# ip_phone_c_codec.net
KiCad netlist of a schematic drawn in Altium Designer
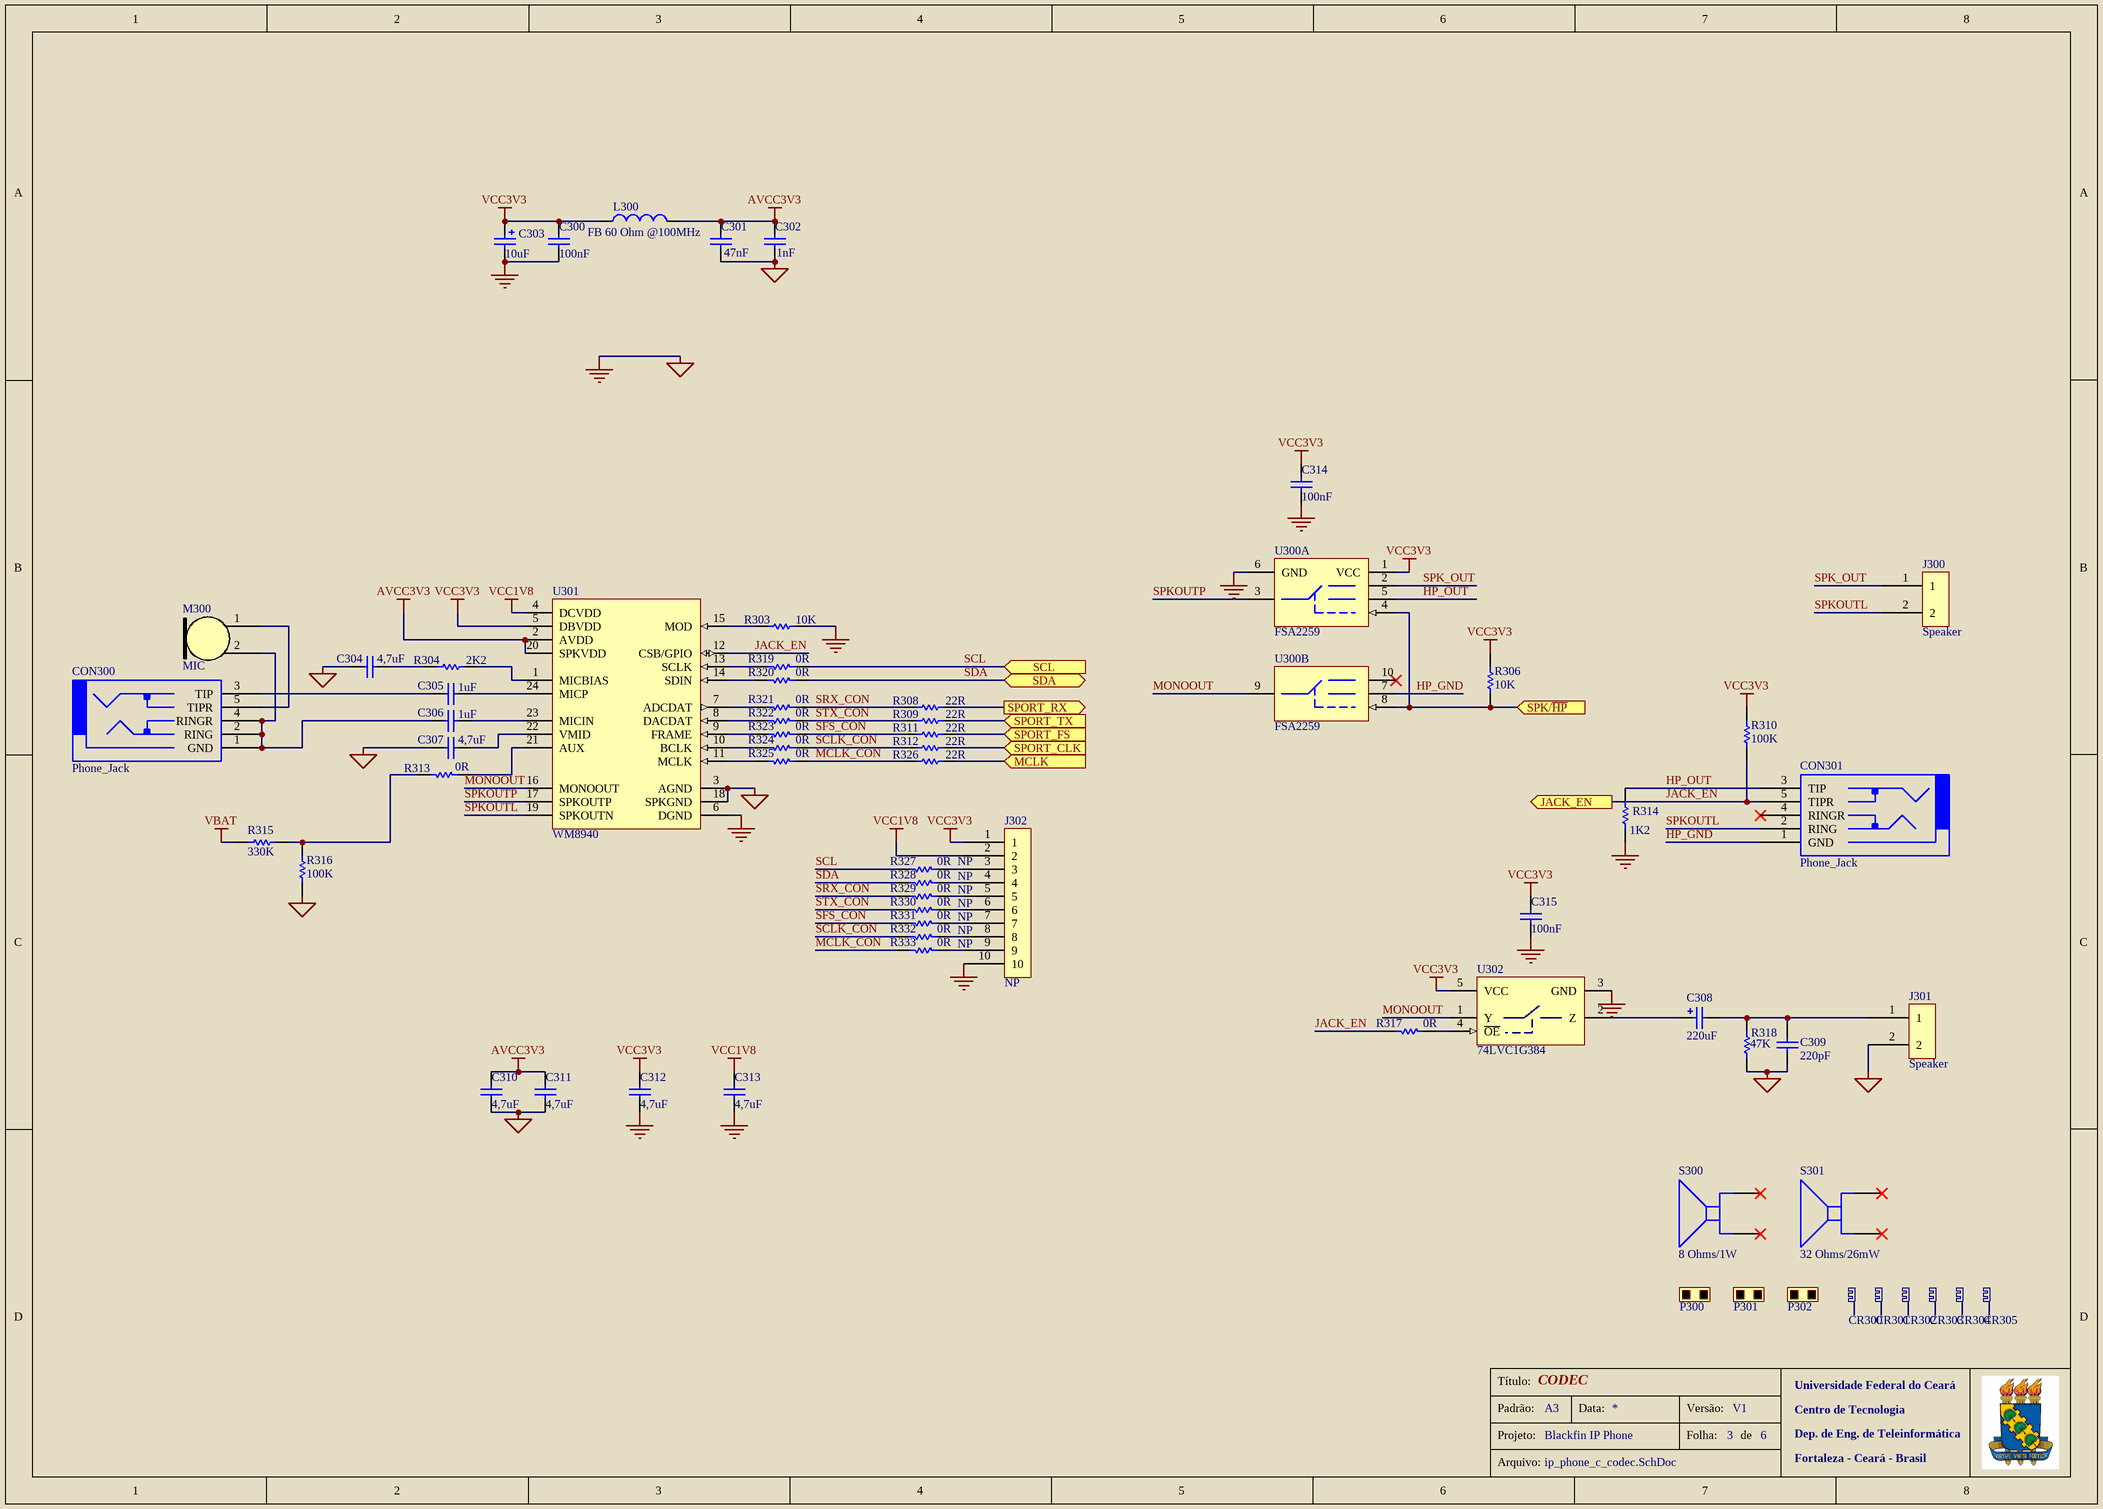
[diagram p0: ip_phone_c_codec.SchDoc]

(export (version "E")
  (design (tool "Eeschema 10.0.6"))
  (components
    (comp (ref "C300")
      (value "100nF")
      (footprint "ip_phone:CC1005-0402")
      (description "MLCC - SMD/SMT 100nF 16V 10% 0402")
      (fields (field (name "EVENDORPART#") "810-C1005X7R1C104K") (field (name "MANUFACTURER") "TDK"))
      (libsource (lib "ip_phone") (part "Capacitor"))
    )
    (comp (ref "C301")
      (value "47nF")
      (footprint "ip_phone:CC1005-0402")
      (description "MLCC - SMD/SMT 47nF 16V 10% 0402")
      (fields (field (name "EVENDORPART#") "311-1334-1-ND") (field (name "MANUFACTURER") "Yageo"))
      (libsource (lib "ip_phone") (part "Capacitor"))
    )
    (comp (ref "C302")
      (value "1nF")
      (footprint "ip_phone:CC1005-0402")
      (description "MLCC - SMD/SMT 1nF 16V 10% 0402")
      (fields (field (name "EVENDORPART#") "311-1352-1-ND") (field (name "MANUFACTURER") "Yageo"))
      (libsource (lib "ip_phone") (part "Capacitor"))
    )
    (comp (ref "C303")
      (value "10uF")
      (footprint "ip_phone:VE-100M0JTR-0305")
      (description "Aluminum Electrolytic Capacitors - SMD 6.3 Volts 10uF 20%")
      (fields (field (name "EVENDORPART#") "140-VE100M0JTR0305") (field (name "PART#") "VE-100M0JTR-0305"))
      (libsource (lib "ip_phone") (part "Capacitor_Electrolytic"))
    )
    (comp (ref "C304")
      (value "4,7uF")
      (footprint "ip_phone:CC1005-0402")
      (description "MLCC - SMD/SMT 4.7uF 20% 6.3Volts 0402")
      (fields (field (name "EVENDORPART#") "810-C1005X5R0J475M") (field (name "MANUFACTURER") "TDK"))
      (libsource (lib "ip_phone") (part "Capacitor"))
    )
    (comp (ref "C305")
      (value "1uF")
      (footprint "ip_phone:CC1005-0402")
      (description "CAP CER 1.0UF 6.3V 20% X5R 0402")
      (fields
        (field (name "EVENDORPART#") "490-1319-1-ND")
        (field (name "MANUFACTURER") "Murata Electronics North America")
      )
      (libsource (lib "ip_phone") (part "Capacitor"))
    )
    (comp (ref "C306")
      (value "1uF")
      (footprint "ip_phone:CC1005-0402")
      (description "CAP CER 1.0UF 6.3V 20% X5R 0402")
      (fields
        (field (name "EVENDORPART#") "490-1319-1-ND")
        (field (name "MANUFACTURER") "Murata Electronics North America")
      )
      (libsource (lib "ip_phone") (part "Capacitor"))
    )
    (comp (ref "C307")
      (value "4,7uF")
      (footprint "ip_phone:CC1005-0402")
      (description "MLCC - SMD/SMT 4.7uF 20% 6.3Volts 0402")
      (fields (field (name "EVENDORPART#") "810-C1005X5R0J475M") (field (name "MANUFACTURER") "TDK"))
      (libsource (lib "ip_phone") (part "Capacitor"))
    )
    (comp (ref "C308")
      (value "220uF")
      (description "Tantalum Capacitor - SMD 6.3 Volts 220uF 10%")
      (fields (field (name "EVENDORPART#") "80-T491D227K006") (field (name "PART#") "T491D227K006AT"))
      (libsource (lib "ip_phone") (part "Capacitor_Electrolytic"))
    )
    (comp (ref "C309")
      (value "220pF")
      (footprint "ip_phone:CC1005-0402")
      (description "Capacitor 220pF 0402")
      (fields (field (name "EVENDORPART#") "311-1035-1-ND") (field (name "MANUFACTURER") "Yageo"))
      (libsource (lib "ip_phone") (part "Capacitor"))
    )
    (comp (ref "C310")
      (value "4,7uF")
      (footprint "ip_phone:CC1005-0402")
      (description "MLCC - SMD/SMT 4.7uF 20% 6.3Volts 0402")
      (fields (field (name "EVENDORPART#") "810-C1005X5R0J475M") (field (name "MANUFACTURER") "TDK"))
      (libsource (lib "ip_phone") (part "Capacitor"))
    )
    (comp (ref "C311")
      (value "4,7uF")
      (footprint "ip_phone:CC1005-0402")
      (description "MLCC - SMD/SMT 4.7uF 20% 6.3Volts 0402")
      (fields (field (name "EVENDORPART#") "810-C1005X5R0J475M") (field (name "MANUFACTURER") "TDK"))
      (libsource (lib "ip_phone") (part "Capacitor"))
    )
    (comp (ref "C312")
      (value "4,7uF")
      (footprint "ip_phone:CC1005-0402")
      (description "MLCC - SMD/SMT 4.7uF 20% 6.3Volts 0402")
      (fields (field (name "EVENDORPART#") "810-C1005X5R0J475M") (field (name "MANUFACTURER") "TDK"))
      (libsource (lib "ip_phone") (part "Capacitor"))
    )
    (comp (ref "C313")
      (value "4,7uF")
      (footprint "ip_phone:CC1005-0402")
      (description "MLCC - SMD/SMT 4.7uF 20% 6.3Volts 0402")
      (fields (field (name "EVENDORPART#") "810-C1005X5R0J475M") (field (name "MANUFACTURER") "TDK"))
      (libsource (lib "ip_phone") (part "Capacitor"))
    )
    (comp (ref "C314")
      (value "100nF")
      (footprint "ip_phone:CC1005-0402")
      (description "MLCC - SMD/SMT 0.1UF 16V 10% 0402")
      (fields (field (name "EVENDORPART#") "810-C1005X7R1C104K") (field (name "MANUFACTURER") "TDK"))
      (libsource (lib "ip_phone") (part "Capacitor"))
    )
    (comp (ref "C315")
      (value "100nF")
      (footprint "ip_phone:CC1005-0402")
      (description "MLCC - SMD/SMT 0.1UF 16V 10% 0402")
      (fields (field (name "EVENDORPART#") "810-C1005X7R1C104K") (field (name "MANUFACTURER") "TDK"))
      (libsource (lib "ip_phone") (part "Capacitor"))
    )
    (comp (ref "CON300")
      (value "Phone_Jack")
      (footprint "ip_phone:Phone_Jack")
      (fields
        (field (name "EVENDORPART#") "CP1-2535SJCT-ND")
        (field (name "MANUFACTURER") "CUI Inc")
        (field (name "PART#") "SJ1-2535-SMT")
      )
      (libsource (lib "ip_phone") (part "Phone_Jack_1"))
    )
    (comp (ref "CON301")
      (value "Phone_Jack")
      (footprint "ip_phone:Phone_Jack")
      (fields
        (field (name "EVENDORPART#") "CP1-2535SJCT-ND")
        (field (name "MANUFACTURER") "CUI Inc")
        (field (name "PART#") "SJ1-2535-SMT")
      )
      (libsource (lib "") (part "Phone_Jack_1_1"))
    )
    (comp (ref "CR300")
      (value "Crimp")
      (description "Socket Crimp")
      (fields (field (name "EVENDORPART#") "656-ILZC3A115000") (field (name "PART#") "IL-Z-C3-A-1-15000"))
      (libsource (lib "ip_phone") (part "Crimp"))
    )
    (comp (ref "CR301")
      (value "Crimp")
      (description "Socket Crimp")
      (fields (field (name "EVENDORPART#") "656-ILZC3A115000") (field (name "PART#") "IL-Z-C3-A-1-15000"))
      (libsource (lib "ip_phone") (part "Crimp"))
    )
    (comp (ref "CR302")
      (value "Crimp")
      (description "Socket Crimp")
      (fields (field (name "EVENDORPART#") "656-ILZC3A115000") (field (name "PART#") "IL-Z-C3-A-1-15000"))
      (libsource (lib "ip_phone") (part "Crimp"))
    )
    (comp (ref "CR303")
      (value "Crimp")
      (description "Socket Crimp")
      (fields (field (name "EVENDORPART#") "656-ILZC3A115000") (field (name "PART#") "IL-Z-C3-A-1-15000"))
      (libsource (lib "ip_phone") (part "Crimp"))
    )
    (comp (ref "CR304")
      (value "Crimp")
      (description "Socket Crimp")
      (fields (field (name "EVENDORPART#") "656-ILZC3A115000") (field (name "PART#") "IL-Z-C3-A-1-15000"))
      (libsource (lib "ip_phone") (part "Crimp"))
    )
    (comp (ref "CR305")
      (value "Crimp")
      (description "Socket Crimp")
      (fields (field (name "EVENDORPART#") "656-ILZC3A115000") (field (name "PART#") "IL-Z-C3-A-1-15000"))
      (libsource (lib "ip_phone") (part "Crimp"))
    )
    (comp (ref "J300")
      (value "Speaker")
      (footprint "ip_phone:CON_IL-Z-2PL")
      (description "Connector 2 Pin 1.25mm Male")
      (fields
        (field (name "EVENDORPART#") "656-IL-Z-2PL-SMTYE")
        (field (name "MANUFACTURER") "JAE Electronics")
      )
      (libsource (lib "ip_phone") (part "Speaker_con"))
    )
    (comp (ref "J301")
      (value "Speaker")
      (footprint "ip_phone:CON_IL-Z-2PL")
      (description "Connector 2 Pin 1.25mm Male")
      (fields
        (field (name "EVENDORPART#") "656-IL-Z-2PL-SMTYE")
        (field (name "MANUFACTURER") "JAE Electronics")
      )
      (libsource (lib "ip_phone") (part "Speaker_con"))
    )
    (comp (ref "J302")
      (value "CONN HEADER")
      (footprint "ip_phone:CONECTOR_10_PIN")
      (description "CONN HEADER .050\" 10POS PCB GOLD")
      (fields
        (field (name "EVENDORPART#") "S9014E-10-ND")
        (field (name "MANUFACTURER") "Sullins Connector Solutions")
        (field (name "NP") "NP")
      )
      (libsource (lib "ip_phone") (part "Conector 10pin"))
    )
    (comp (ref "L300")
      (value "FB 60 Ohm @100MHz")
      (footprint "ip_phone:INDUTOR_0603")
      (description "Ferrite Bead 60 Ohm @100MHz")
      (fields
        (field (name "EVENDORPART#") "667-EXC-3BP600H")
        (field (name "MANUFACTURER") "Panasonic Electronic Components")
      )
      (libsource (lib "ip_phone") (part "Inductor"))
    )
    (comp (ref "M300")
      (value "MIC")
      (footprint "ip_phone:CON_IL-Z-2PL")
      (description "Microphones -38DB 2VDC .5MA 2.2KOHM")
      (fields (field (name "PART#") "POM-2738P-C33-R") (field (name "MANUFACTURER") "PUI Audio"))
      (libsource (lib "ip_phone") (part "MIC"))
    )
    (comp (ref "P300")
      (value "Socket Housing")
      (description "Socket Housing 1.25mm 2 Pins")
      (fields (field (name "EVENDORPART#") "656-IL-Z-2S-S125C3") (field (name "PART#") "IL-Z-2S-S125C3"))
      (libsource (lib "ip_phone") (part "Socket Housing"))
    )
    (comp (ref "P301")
      (value "Socket Housing")
      (description "Socket Housing 1.25mm 2 Pins")
      (fields (field (name "EVENDORPART#") "656-IL-Z-2S-S125C3") (field (name "PART#") "IL-Z-2S-S125C3"))
      (libsource (lib "ip_phone") (part "Socket Housing"))
    )
    (comp (ref "P302")
      (value "Socket Housing")
      (description "Socket Housing 1.25mm 2 Pins")
      (fields (field (name "EVENDORPART#") "656-IL-Z-2S-S125C3") (field (name "PART#") "IL-Z-2S-S125C3"))
      (libsource (lib "ip_phone") (part "Socket Housing"))
    )
    (comp (ref "R303")
      (value "10K")
      (footprint "ip_phone:CR1005-0402")
      (description "Thick Film Resistors SMD 0402 10K 5%  1/16 W")
      (fields (field (name "EVENDORPART#") "311-10KJRCT-ND") (field (name "MANUFACTURER") "Yageo"))
      (libsource (lib "ip_phone") (part "Resistor"))
    )
    (comp (ref "R304")
      (value "2K2")
      (footprint "ip_phone:CR1005-0402")
      (description "Thick Film Resistors SMD 0402 2K2 5%  1/16 W")
      (fields (field (name "EVENDORPART#") "311-2.2KJRCT-ND") (field (name "MANUFACTURER") "Yageo"))
      (libsource (lib "ip_phone") (part "Resistor"))
    )
    (comp (ref "R306")
      (value "10K")
      (footprint "ip_phone:CR1005-0402")
      (description "Thick Film Resistors SMD 0402 10K 5%  1/16 W")
      (fields (field (name "EVENDORPART#") "311-10KJRCT-ND") (field (name "MANUFACTURER") "Yageo"))
      (libsource (lib "ip_phone") (part "Resistor"))
    )
    (comp (ref "R308")
      (value "22R")
      (footprint "ip_phone:CR1005-0402")
      (description "Thick Film Resistors SMD 0402 22R 5%  1/16 W")
      (fields (field (name "EVENDORPART#") "71-CRCW0402J-22-E3") (field (name "MANUFACTURER") "Vishay/Dale"))
      (libsource (lib "ip_phone") (part "Resistor"))
    )
    (comp (ref "R309")
      (value "22R")
      (footprint "ip_phone:CR1005-0402")
      (description "Thick Film Resistors SMD 0402 22R 5%  1/16 W")
      (fields (field (name "EVENDORPART#") "71-CRCW0402J-22-E3") (field (name "MANUFACTURER") "Vishay/Dale"))
      (libsource (lib "ip_phone") (part "Resistor"))
    )
    (comp (ref "R310")
      (value "100K")
      (footprint "ip_phone:CR1005-0402")
      (description "Thick Film Resistors SMD 0402 100K 5%  1/16 W")
      (fields (field (name "EVENDORPART#") "311-100KJRCT-ND") (field (name "MANUFACTURER") "Yageo"))
      (libsource (lib "ip_phone") (part "Resistor"))
    )
    (comp (ref "R311")
      (value "22R")
      (footprint "ip_phone:CR1005-0402")
      (description "Thick Film Resistors SMD 0402 22R 5%  1/16 W")
      (fields (field (name "EVENDORPART#") "71-CRCW0402J-22-E3") (field (name "MANUFACTURER") "Vishay/Dale"))
      (libsource (lib "ip_phone") (part "Resistor"))
    )
    (comp (ref "R312")
      (value "22R")
      (footprint "ip_phone:CR1005-0402")
      (description "Thick Film Resistors SMD 0402 22R 5%  1/16 W")
      (fields (field (name "EVENDORPART#") "71-CRCW0402J-22-E3") (field (name "MANUFACTURER") "Vishay/Dale"))
      (libsource (lib "ip_phone") (part "Resistor"))
    )
    (comp (ref "R313")
      (value "0R")
      (footprint "ip_phone:CR1005-0402")
      (description "Thick Film Resistors 0402 1/16W Jumper")
      (fields
        (field (name "EVENDORPART#") "667-ERJ-2GE0R00X")
        (field (name "MANUFACTURER") "Panasonic Electronic Components")
      )
      (libsource (lib "ip_phone") (part "Resistor"))
    )
    (comp (ref "R314")
      (value "1K2")
      (footprint "ip_phone:CR1005-0402")
      (description "Thick Film Resistors SMD 0402 1K2 5%  1/16 W")
      (fields (field (name "EVENDORPART#") "311-1.2KJRCT-ND") (field (name "MANUFACTURER") "Yageo"))
      (libsource (lib "ip_phone") (part "Resistor"))
    )
    (comp (ref "R315")
      (value "330K")
      (footprint "ip_phone:CR1005-0402")
      (description "Thick Film Resistor 330K 1% 1/16W")
      (fields
        (field (name "EVENDORPART#") "RMCF0402FT330KCT-ND")
        (field (name "MANUFACTURER") "Stackpole Electronics Inc")
      )
      (libsource (lib "ip_phone") (part "Resistor"))
    )
    (comp (ref "R316")
      (value "100K")
      (footprint "ip_phone:CR1005-0402")
      (description "Thick Film Resistors SMD 0402 100K 5%  1/16 W")
      (fields (field (name "EVENDORPART#") "311-100KJRCT-ND") (field (name "MANUFACTURER") "Yageo"))
      (libsource (lib "ip_phone") (part "Resistor"))
    )
    (comp (ref "R317")
      (value "0R")
      (footprint "ip_phone:CR1005-0402")
      (description "Thick Film Resistors 0402 1/16W Jumper")
      (fields
        (field (name "EVENDORPART#") "667-ERJ-2GE0R00X")
        (field (name "MANUFACTURER") "Panasonic Electronic Components")
      )
      (libsource (lib "ip_phone") (part "Resistor"))
    )
    (comp (ref "R318")
      (value "47K")
      (footprint "ip_phone:CR1005-0402")
      (description "Thick Film Resistors SMD 0402 47K 5%  1/16 W")
      (fields (field (name "EVENDORPART#") "311-47KJRCT-ND") (field (name "MANUFACTURER") "Yageo"))
      (libsource (lib "ip_phone") (part "Resistor"))
    )
    (comp (ref "R319")
      (value "0R")
      (footprint "ip_phone:CR1005-0402")
      (description "Thick Film Resistors 0402 1/16W Jumper")
      (fields
        (field (name "EVENDORPART#") "667-ERJ-2GE0R00X")
        (field (name "MANUFACTURER") "Panasonic Electronic Components")
      )
      (libsource (lib "ip_phone") (part "Resistor"))
    )
    (comp (ref "R320")
      (value "0R")
      (footprint "ip_phone:CR1005-0402")
      (description "Thick Film Resistors 0402 1/16W Jumper")
      (fields
        (field (name "EVENDORPART#") "667-ERJ-2GE0R00X")
        (field (name "MANUFACTURER") "Panasonic Electronic Components")
      )
      (libsource (lib "ip_phone") (part "Resistor"))
    )
    (comp (ref "R321")
      (value "0R")
      (footprint "ip_phone:CR1005-0402")
      (description "Thick Film Resistors 0402 1/16W Jumper")
      (fields
        (field (name "EVENDORPART#") "667-ERJ-2GE0R00X")
        (field (name "MANUFACTURER") "Panasonic Electronic Components")
      )
      (libsource (lib "ip_phone") (part "Resistor"))
    )
    (comp (ref "R322")
      (value "0R")
      (footprint "ip_phone:CR1005-0402")
      (description "Thick Film Resistors 0402 1/16W Jumper")
      (fields
        (field (name "EVENDORPART#") "667-ERJ-2GE0R00X")
        (field (name "MANUFACTURER") "Panasonic Electronic Components")
      )
      (libsource (lib "ip_phone") (part "Resistor"))
    )
    (comp (ref "R323")
      (value "0R")
      (footprint "ip_phone:CR1005-0402")
      (description "Thick Film Resistors 0402 1/16W Jumper")
      (fields
        (field (name "EVENDORPART#") "667-ERJ-2GE0R00X")
        (field (name "MANUFACTURER") "Panasonic Electronic Components")
      )
      (libsource (lib "ip_phone") (part "Resistor"))
    )
    (comp (ref "R324")
      (value "0R")
      (footprint "ip_phone:CR1005-0402")
      (description "Thick Film Resistors 0402 1/16W Jumper")
      (fields
        (field (name "EVENDORPART#") "667-ERJ-2GE0R00X")
        (field (name "MANUFACTURER") "Panasonic Electronic Components")
      )
      (libsource (lib "ip_phone") (part "Resistor"))
    )
    (comp (ref "R325")
      (value "0R")
      (footprint "ip_phone:CR1005-0402")
      (description "Thick Film Resistors 0402 1/16W Jumper")
      (fields
        (field (name "EVENDORPART#") "667-ERJ-2GE0R00X")
        (field (name "MANUFACTURER") "Panasonic Electronic Components")
      )
      (libsource (lib "ip_phone") (part "Resistor"))
    )
    (comp (ref "R326")
      (value "22R")
      (footprint "ip_phone:CR1005-0402")
      (description "Thick Film Resistors SMD 0402 22R 5%  1/16 W")
      (fields (field (name "EVENDORPART#") "71-CRCW0402J-22-E3") (field (name "MANUFACTURER") "Vishay/Dale"))
      (libsource (lib "ip_phone") (part "Resistor"))
    )
    (comp (ref "R327")
      (value "0R")
      (footprint "ip_phone:CR1005-0402")
      (description "Thick Film Resistors 0402 1/16W Jumper")
      (fields
        (field (name "EVENDORPART#") "667-ERJ-2GE0R00X")
        (field (name "MANUFACTURER") "Panasonic Electronic Components")
        (field (name "NP") "NP")
      )
      (libsource (lib "ip_phone") (part "Resistor"))
    )
    (comp (ref "R328")
      (value "0R")
      (footprint "ip_phone:CR1005-0402")
      (description "Thick Film Resistors 0402 1/16W Jumper")
      (fields
        (field (name "EVENDORPART#") "667-ERJ-2GE0R00X")
        (field (name "MANUFACTURER") "Panasonic Electronic Components")
        (field (name "NP") "NP")
      )
      (libsource (lib "ip_phone") (part "Resistor"))
    )
    (comp (ref "R329")
      (value "0R")
      (footprint "ip_phone:CR1005-0402")
      (description "Thick Film Resistors 0402 1/16W Jumper")
      (fields
        (field (name "EVENDORPART#") "667-ERJ-2GE0R00X")
        (field (name "MANUFACTURER") "Panasonic Electronic Components")
        (field (name "NP") "NP")
      )
      (libsource (lib "ip_phone") (part "Resistor"))
    )
    (comp (ref "R330")
      (value "0R")
      (footprint "ip_phone:CR1005-0402")
      (description "Thick Film Resistors 0402 1/16W Jumper")
      (fields
        (field (name "EVENDORPART#") "667-ERJ-2GE0R00X")
        (field (name "MANUFACTURER") "Panasonic Electronic Components")
        (field (name "NP") "NP")
      )
      (libsource (lib "ip_phone") (part "Resistor"))
    )
    (comp (ref "R331")
      (value "0R")
      (footprint "ip_phone:CR1005-0402")
      (description "Thick Film Resistors 0402 1/16W Jumper")
      (fields
        (field (name "EVENDORPART#") "667-ERJ-2GE0R00X")
        (field (name "MANUFACTURER") "Panasonic Electronic Components")
        (field (name "NP") "NP")
      )
      (libsource (lib "ip_phone") (part "Resistor"))
    )
    (comp (ref "R332")
      (value "0R")
      (footprint "ip_phone:CR1005-0402")
      (description "Thick Film Resistors 0402 1/16W Jumper")
      (fields
        (field (name "EVENDORPART#") "667-ERJ-2GE0R00X")
        (field (name "MANUFACTURER") "Panasonic Electronic Components")
        (field (name "NP") "NP")
      )
      (libsource (lib "ip_phone") (part "Resistor"))
    )
    (comp (ref "R333")
      (value "0R")
      (footprint "ip_phone:CR1005-0402")
      (description "Thick Film Resistors 0402 1/16W Jumper")
      (fields
        (field (name "EVENDORPART#") "667-ERJ-2GE0R00X")
        (field (name "MANUFACTURER") "Panasonic Electronic Components")
        (field (name "NP") "NP")
      )
      (libsource (lib "ip_phone") (part "Resistor"))
    )
    (comp (ref "S300")
      (value "8 Ohms/1W")
      (description "Speaker 8 Ohms 1W")
      (fields (field (name "EVENDORPART#") "254-DS238-RO") (field (name "MANUFACTURER") "Kobitone"))
      (libsource (lib "ip_phone") (part "Speaker"))
    )
    (comp (ref "S301")
      (value "32 Ohms/26mW")
      (description "Dynamic Receiver 32Ohms 26mW 115dB 13mm D")
      (fields (field (name "EVENDORPART#") "254-DR132-RO") (field (name "MANUFACTURER") "Kobitone"))
      (libsource (lib "ip_phone") (part "Receiver"))
    )
    (comp (ref "U300")
      (value "FSA2259")
      (footprint "ip_phone:QFN-10FSA")
      (description "Analog Switch, Dual SPDT")
      (fields
        (field (name "EVENDORPART#") "512-FSA2259UMX")
        (field (name "MANUFACTURER") "Fairchild Semiconductor")
      )
      (libsource (lib "ip_phone") (part "FSA2259"))
    )
    (comp (ref "U301")
      (value "WM8940")
      (footprint "ip_phone:QFN24")
      (description "Mono Audio CODEC")
      (fields (field (name "EVENDORPART#") "238-WM8940GEFL/V") (field (name "PART#") "WM8940GEFL/V"))
      (libsource (lib "ip_phone") (part "WM8940"))
    )
    (comp (ref "U302")
      (value "74LVC1G384")
      (footprint "ip_phone:SOT753")
      (description "Low Voltage SPST Analog Switch")
      (fields (field (name "EVENDORPART#") "771-LVC1G384GV125") (field (name "PART#") "74LVC1G384GV,125"))
      (libsource (lib "ip_phone") (part "74LVC1G384"))
    )
  )
  (nets
    (net (code "1") (name "/HP_GND") (class "Default")
      (node (ref "CON301") (pin "1") (pinfunction "GND_1") (pintype "passive"))
      (node (ref "U300") (pin "7") (pinfunction "2B0_7") (pintype "passive"))
    )
    (net (code "2") (name "/HP_OUT") (class "Default")
      (node (ref "CON301") (pin "3") (pinfunction "TIP_3") (pintype "passive"))
      (node (ref "R314") (pin "1") (pinfunction "1_1") (pintype "passive"))
      (node (ref "U300") (pin "5") (pinfunction "1B0_5") (pintype "passive"))
    )
    (net (code "3") (name "/JACK_EN") (class "Default")
      (node (ref "CON301") (pin "5") (pinfunction "TIPR_5") (pintype "passive"))
      (node (ref "R310") (pin "1") (pinfunction "1_1") (pintype "passive"))
      (node (ref "R317") (pin "2") (pinfunction "2_2") (pintype "passive"))
      (node (ref "U301") (pin "12") (pinfunction "CSB/GPIO_12") (pintype "bidirectional"))
    )
    (net (code "4") (name "/MCLK") (class "Default")
      (node (ref "R326") (pin "2") (pinfunction "2_2") (pintype "passive"))
    )
    (net (code "5") (name "/MCLK_CON") (class "Default")
      (node (ref "R325") (pin "1") (pinfunction "1_1") (pintype "passive"))
      (node (ref "R326") (pin "1") (pinfunction "1_1") (pintype "passive"))
      (node (ref "R333") (pin "2") (pinfunction "2_2") (pintype "passive"))
    )
    (net (code "6") (name "/MONOOUT") (class "Default")
      (node (ref "U300") (pin "9") (pinfunction "2A_9") (pintype "passive"))
      (node (ref "U301") (pin "16") (pinfunction "MONOOUT_16") (pintype "passive"))
      (node (ref "U302") (pin "1") (pinfunction "Y_1") (pintype "passive"))
    )
    (net (code "7") (name "/SCL") (class "Default")
      (node (ref "R319") (pin "1") (pinfunction "1_1") (pintype "passive"))
      (node (ref "R327") (pin "2") (pinfunction "2_2") (pintype "passive"))
    )
    (net (code "8") (name "/SCLK_CON") (class "Default")
      (node (ref "R312") (pin "1") (pinfunction "1_1") (pintype "passive"))
      (node (ref "R324") (pin "1") (pinfunction "1_1") (pintype "passive"))
      (node (ref "R332") (pin "2") (pinfunction "2_2") (pintype "passive"))
    )
    (net (code "9") (name "/SDA") (class "Default")
      (node (ref "R320") (pin "1") (pinfunction "1_1") (pintype "passive"))
      (node (ref "R328") (pin "2") (pinfunction "2_2") (pintype "passive"))
    )
    (net (code "10") (name "/SFS_CON") (class "Default")
      (node (ref "R311") (pin "1") (pinfunction "1_1") (pintype "passive"))
      (node (ref "R323") (pin "1") (pinfunction "1_1") (pintype "passive"))
      (node (ref "R331") (pin "2") (pinfunction "2_2") (pintype "passive"))
    )
    (net (code "11") (name "/SPKOUTL") (class "Default")
      (node (ref "CON301") (pin "2") (pinfunction "RING_2") (pintype "passive"))
      (node (ref "J300") (pin "2") (pinfunction "2_2") (pintype "passive"))
      (node (ref "U301") (pin "19") (pinfunction "SPKOUTN_19") (pintype "passive"))
    )
    (net (code "12") (name "/SPKOUTP") (class "Default")
      (node (ref "U300") (pin "3") (pinfunction "1A_3") (pintype "passive"))
      (node (ref "U301") (pin "17") (pinfunction "SPKOUTP_17") (pintype "passive"))
    )
    (net (code "13") (name "/SPK_OUT") (class "Default")
      (node (ref "J300") (pin "1") (pinfunction "1_1") (pintype "passive"))
      (node (ref "U300") (pin "2") (pinfunction "1B1_2") (pintype "passive"))
    )
    (net (code "14") (name "/SPK{slash}~{HP}") (class "Default")
      (node (ref "R306") (pin "1") (pinfunction "1_1") (pintype "passive"))
      (node (ref "U300") (pin "4") (pinfunction "S1_4") (pintype "input"))
      (node (ref "U300") (pin "8") (pinfunction "S2_8") (pintype "input"))
    )
    (net (code "15") (name "/SPORT_CLK") (class "Default")
      (node (ref "R312") (pin "2") (pinfunction "2_2") (pintype "passive"))
    )
    (net (code "16") (name "/SPORT_FS") (class "Default")
      (node (ref "R311") (pin "2") (pinfunction "2_2") (pintype "passive"))
    )
    (net (code "17") (name "/SPORT_RX") (class "Default")
      (node (ref "R308") (pin "2") (pinfunction "2_2") (pintype "passive"))
    )
    (net (code "18") (name "/SPORT_TX") (class "Default")
      (node (ref "R309") (pin "2") (pinfunction "2_2") (pintype "passive"))
    )
    (net (code "19") (name "/SRX_CON") (class "Default")
      (node (ref "R308") (pin "1") (pinfunction "1_1") (pintype "passive"))
      (node (ref "R321") (pin "1") (pinfunction "1_1") (pintype "passive"))
      (node (ref "R329") (pin "2") (pinfunction "2_2") (pintype "passive"))
    )
    (net (code "20") (name "/STX_CON") (class "Default")
      (node (ref "R309") (pin "1") (pinfunction "1_1") (pintype "passive"))
      (node (ref "R322") (pin "1") (pinfunction "1_1") (pintype "passive"))
      (node (ref "R330") (pin "2") (pinfunction "2_2") (pintype "passive"))
    )
    (net (code "21") (name "AGND") (class "Default")
      (node (ref "C300") (pin "1") (pinfunction "1_1") (pintype "passive"))
      (node (ref "C301") (pin "1") (pinfunction "1_1") (pintype "passive"))
      (node (ref "C302") (pin "1") (pinfunction "1_1") (pintype "passive"))
      (node (ref "C303") (pin "2") (pinfunction "2_2") (pintype "passive"))
      (node (ref "C304") (pin "1") (pinfunction "1_1") (pintype "passive"))
      (node (ref "C307") (pin "1") (pinfunction "1_1") (pintype "passive"))
      (node (ref "C309") (pin "1") (pinfunction "1_1") (pintype "passive"))
      (node (ref "C310") (pin "2") (pinfunction "2_2") (pintype "passive"))
      (node (ref "C311") (pin "2") (pinfunction "2_2") (pintype "passive"))
      (node (ref "C312") (pin "2") (pinfunction "2_2") (pintype "passive"))
      (node (ref "C313") (pin "2") (pinfunction "2_2") (pintype "passive"))
      (node (ref "C314") (pin "1") (pinfunction "1_1") (pintype "passive"))
      (node (ref "C315") (pin "1") (pinfunction "1_1") (pintype "passive"))
      (node (ref "J301") (pin "2") (pinfunction "2_2") (pintype "passive"))
      (node (ref "J302") (pin "10") (pinfunction "10_10") (pintype "passive"))
      (node (ref "R303") (pin "2") (pinfunction "2_2") (pintype "passive"))
      (node (ref "R314") (pin "2") (pinfunction "2_2") (pintype "passive"))
      (node (ref "R316") (pin "1") (pinfunction "1_1") (pintype "passive"))
      (node (ref "R318") (pin "2") (pinfunction "2_2") (pintype "passive"))
      (node (ref "U300") (pin "6") (pinfunction "GND_6") (pintype "power_in"))
      (node (ref "U301") (pin "18") (pinfunction "SPKGND_18") (pintype "passive"))
      (node (ref "U301") (pin "3") (pinfunction "AGND_3") (pintype "power_in"))
      (node (ref "U301") (pin "6") (pinfunction "DGND_6") (pintype "power_in"))
      (node (ref "U302") (pin "3") (pinfunction "GND_3") (pintype "power_in"))
    )
    (net (code "22") (name "AVCC3V3") (class "Default")
      (node (ref "C301") (pin "2") (pinfunction "2_2") (pintype "passive"))
      (node (ref "C302") (pin "2") (pinfunction "2_2") (pintype "passive"))
      (node (ref "C310") (pin "1") (pinfunction "1_1") (pintype "passive"))
      (node (ref "C311") (pin "1") (pinfunction "1_1") (pintype "passive"))
      (node (ref "L300") (pin "2") (pinfunction "2_2") (pintype "passive"))
      (node (ref "U301") (pin "2") (pinfunction "AVDD_2") (pintype "power_in"))
      (node (ref "U301") (pin "20") (pinfunction "SPKVDD_20") (pintype "power_in"))
    )
    (net (code "23") (name "Net-(C304-Pad2)") (class "Default")
      (node (ref "C304") (pin "2") (pinfunction "2_2") (pintype "passive"))
      (node (ref "R304") (pin "1") (pinfunction "1_1") (pintype "passive"))
    )
    (net (code "24") (name "Net-(C308-Pad2)") (class "Default")
      (node (ref "C308") (pin "2") (pinfunction "2_2") (pintype "passive"))
      (node (ref "C309") (pin "2") (pinfunction "2_2") (pintype "passive"))
      (node (ref "J301") (pin "1") (pinfunction "1_1") (pintype "passive"))
      (node (ref "R318") (pin "1") (pinfunction "1_1") (pintype "passive"))
    )
    (net (code "25") (name "Net-(CON300-GND)") (class "Default")
      (node (ref "C306") (pin "2") (pinfunction "2_2") (pintype "passive"))
      (node (ref "CON300") (pin "1") (pinfunction "GND_1") (pintype "passive"))
      (node (ref "CON300") (pin "2") (pinfunction "RING_2") (pintype "passive"))
      (node (ref "CON300") (pin "4") (pinfunction "RINGR_4") (pintype "passive"))
      (node (ref "M300") (pin "2") (pinfunction "GND_2") (pintype "power_in"))
    )
    (net (code "26") (name "Net-(CON300-TIP)") (class "Default")
      (node (ref "C305") (pin "2") (pinfunction "2_2") (pintype "passive"))
      (node (ref "CON300") (pin "3") (pinfunction "TIP_3") (pintype "passive"))
    )
    (net (code "27") (name "Net-(CON300-TIPR)") (class "Default")
      (node (ref "CON300") (pin "5") (pinfunction "TIPR_5") (pintype "passive"))
      (node (ref "M300") (pin "1") (pinfunction "OUT_1") (pintype "passive"))
    )
    (net (code "28") (name "Net-(J302-Pad3)") (class "Default")
      (node (ref "J302") (pin "3") (pinfunction "3_3") (pintype "passive"))
      (node (ref "R327") (pin "1") (pinfunction "1_1") (pintype "passive"))
    )
    (net (code "29") (name "Net-(J302-Pad4)") (class "Default")
      (node (ref "J302") (pin "4") (pinfunction "4_4") (pintype "passive"))
      (node (ref "R328") (pin "1") (pinfunction "1_1") (pintype "passive"))
    )
    (net (code "30") (name "Net-(J302-Pad5)") (class "Default")
      (node (ref "J302") (pin "5") (pinfunction "5_5") (pintype "passive"))
      (node (ref "R329") (pin "1") (pinfunction "1_1") (pintype "passive"))
    )
    (net (code "31") (name "Net-(J302-Pad6)") (class "Default")
      (node (ref "J302") (pin "6") (pinfunction "6_6") (pintype "passive"))
      (node (ref "R330") (pin "1") (pinfunction "1_1") (pintype "passive"))
    )
    (net (code "32") (name "Net-(J302-Pad7)") (class "Default")
      (node (ref "J302") (pin "7") (pinfunction "7_7") (pintype "passive"))
      (node (ref "R331") (pin "1") (pinfunction "1_1") (pintype "passive"))
    )
    (net (code "33") (name "Net-(J302-Pad8)") (class "Default")
      (node (ref "J302") (pin "8") (pinfunction "8_8") (pintype "passive"))
      (node (ref "R332") (pin "1") (pinfunction "1_1") (pintype "passive"))
    )
    (net (code "34") (name "Net-(J302-Pad9)") (class "Default")
      (node (ref "J302") (pin "9") (pinfunction "9_9") (pintype "passive"))
      (node (ref "R333") (pin "1") (pinfunction "1_1") (pintype "passive"))
    )
    (net (code "35") (name "Net-(R313-Pad2)") (class "Default")
      (node (ref "R313") (pin "2") (pinfunction "2_2") (pintype "passive"))
      (node (ref "R315") (pin "2") (pinfunction "2_2") (pintype "passive"))
      (node (ref "R316") (pin "2") (pinfunction "2_2") (pintype "passive"))
    )
    (net (code "36") (name "Net-(U301-ADCDAT)") (class "Default")
      (node (ref "R321") (pin "2") (pinfunction "2_2") (pintype "passive"))
      (node (ref "U301") (pin "7") (pinfunction "ADCDAT_7") (pintype "output"))
    )
    (net (code "37") (name "Net-(U301-AUX)") (class "Default")
      (node (ref "R313") (pin "1") (pinfunction "1_1") (pintype "passive"))
      (node (ref "U301") (pin "21") (pinfunction "AUX_21") (pintype "passive"))
    )
    (net (code "38") (name "Net-(U301-BCLK)") (class "Default")
      (node (ref "R324") (pin "2") (pinfunction "2_2") (pintype "passive"))
      (node (ref "U301") (pin "10") (pinfunction "BCLK_10") (pintype "input"))
    )
    (net (code "39") (name "Net-(U301-DACDAT)") (class "Default")
      (node (ref "R322") (pin "2") (pinfunction "2_2") (pintype "passive"))
      (node (ref "U301") (pin "8") (pinfunction "DACDAT_8") (pintype "input"))
    )
    (net (code "40") (name "Net-(U301-FRAME)") (class "Default")
      (node (ref "R323") (pin "2") (pinfunction "2_2") (pintype "passive"))
      (node (ref "U301") (pin "9") (pinfunction "FRAME_9") (pintype "input"))
    )
    (net (code "41") (name "Net-(U301-MCLK)") (class "Default")
      (node (ref "R325") (pin "2") (pinfunction "2_2") (pintype "passive"))
      (node (ref "U301") (pin "11") (pinfunction "MCLK_11") (pintype "input"))
    )
    (net (code "42") (name "Net-(U301-MICBIAS)") (class "Default")
      (node (ref "R304") (pin "2") (pinfunction "2_2") (pintype "passive"))
      (node (ref "U301") (pin "1") (pinfunction "MICBIAS_1") (pintype "passive"))
    )
    (net (code "43") (name "Net-(U301-MICIN)") (class "Default")
      (node (ref "C306") (pin "1") (pinfunction "1_1") (pintype "passive"))
      (node (ref "U301") (pin "23") (pinfunction "MICIN_23") (pintype "passive"))
    )
    (net (code "44") (name "Net-(U301-MICP)") (class "Default")
      (node (ref "C305") (pin "1") (pinfunction "1_1") (pintype "passive"))
      (node (ref "U301") (pin "24") (pinfunction "MICP_24") (pintype "passive"))
    )
    (net (code "45") (name "Net-(U301-MOD)") (class "Default")
      (node (ref "R303") (pin "1") (pinfunction "1_1") (pintype "passive"))
      (node (ref "U301") (pin "15") (pinfunction "MOD_15") (pintype "input"))
    )
    (net (code "46") (name "Net-(U301-SCLK)") (class "Default")
      (node (ref "R319") (pin "2") (pinfunction "2_2") (pintype "passive"))
      (node (ref "U301") (pin "13") (pinfunction "SCLK_13") (pintype "input"))
    )
    (net (code "47") (name "Net-(U301-SDIN)") (class "Default")
      (node (ref "R320") (pin "2") (pinfunction "2_2") (pintype "passive"))
      (node (ref "U301") (pin "14") (pinfunction "SDIN_14") (pintype "input"))
    )
    (net (code "48") (name "Net-(U301-VMID)") (class "Default")
      (node (ref "C307") (pin "2") (pinfunction "2_2") (pintype "passive"))
      (node (ref "U301") (pin "22") (pinfunction "VMID_22") (pintype "passive"))
    )
    (net (code "49") (name "Net-(U302-OE)") (class "Default")
      (node (ref "R317") (pin "1") (pinfunction "1_1") (pintype "passive"))
      (node (ref "U302") (pin "4") (pinfunction "OE_4") (pintype "input"))
    )
    (net (code "50") (name "Net-(U302-Z)") (class "Default")
      (node (ref "C308") (pin "1") (pinfunction "1_1") (pintype "passive"))
      (node (ref "U302") (pin "2") (pinfunction "Z_2") (pintype "passive"))
    )
    (net (code "51") (name "VBAT") (class "Default")
      (node (ref "R315") (pin "1") (pinfunction "1_1") (pintype "passive"))
    )
    (net (code "52") (name "VCC1V8") (class "Default")
      (node (ref "C313") (pin "1") (pinfunction "1_1") (pintype "passive"))
      (node (ref "J302") (pin "2") (pinfunction "2_2") (pintype "passive"))
      (node (ref "U301") (pin "4") (pinfunction "DCVDD_4") (pintype "power_in"))
    )
    (net (code "53") (name "VCC3V3") (class "Default")
      (node (ref "C300") (pin "2") (pinfunction "2_2") (pintype "passive"))
      (node (ref "C303") (pin "1") (pinfunction "1_1") (pintype "passive"))
      (node (ref "C312") (pin "1") (pinfunction "1_1") (pintype "passive"))
      (node (ref "C314") (pin "2") (pinfunction "2_2") (pintype "passive"))
      (node (ref "C315") (pin "2") (pinfunction "2_2") (pintype "passive"))
      (node (ref "J302") (pin "1") (pinfunction "1_1") (pintype "passive"))
      (node (ref "L300") (pin "1") (pinfunction "1_1") (pintype "passive"))
      (node (ref "R306") (pin "2") (pinfunction "2_2") (pintype "passive"))
      (node (ref "R310") (pin "2") (pinfunction "2_2") (pintype "passive"))
      (node (ref "U300") (pin "1") (pinfunction "VCC_1") (pintype "passive"))
      (node (ref "U301") (pin "5") (pinfunction "DBVDD_5") (pintype "power_in"))
      (node (ref "U302") (pin "5") (pinfunction "VCC_5") (pintype "power_in"))
    )
    (net (code "54") (name "unconnected-(CON301-RINGR-Pad4)") (class "Default")
      (node (ref "CON301") (pin "4") (pinfunction "RINGR_4") (pintype "passive+no_connect"))
    )
    (net (code "55") (name "unconnected-(S300-CKT1-Pad1)") (class "Default")
      (node (ref "S300") (pin "1") (pinfunction "CKT1_1") (pintype "passive+no_connect"))
    )
    (net (code "56") (name "unconnected-(S300-CKT2-Pad2)") (class "Default")
      (node (ref "S300") (pin "2") (pinfunction "CKT2_2") (pintype "passive+no_connect"))
    )
    (net (code "57") (name "unconnected-(S301-CKT1-Pad1)") (class "Default")
      (node (ref "S301") (pin "1") (pinfunction "CKT1_1") (pintype "passive+no_connect"))
    )
    (net (code "58") (name "unconnected-(S301-CKT2-Pad2)") (class "Default")
      (node (ref "S301") (pin "2") (pinfunction "CKT2_2") (pintype "passive+no_connect"))
    )
    (net (code "59") (name "unconnected-(U300B-2B1-Pad10)") (class "Default")
      (node (ref "U300") (pin "10") (pinfunction "2B1_10") (pintype "passive+no_connect"))
    )
  )
)
